# 1_-_POWER.net
KiCad netlist of a schematic drawn in Altium Designer
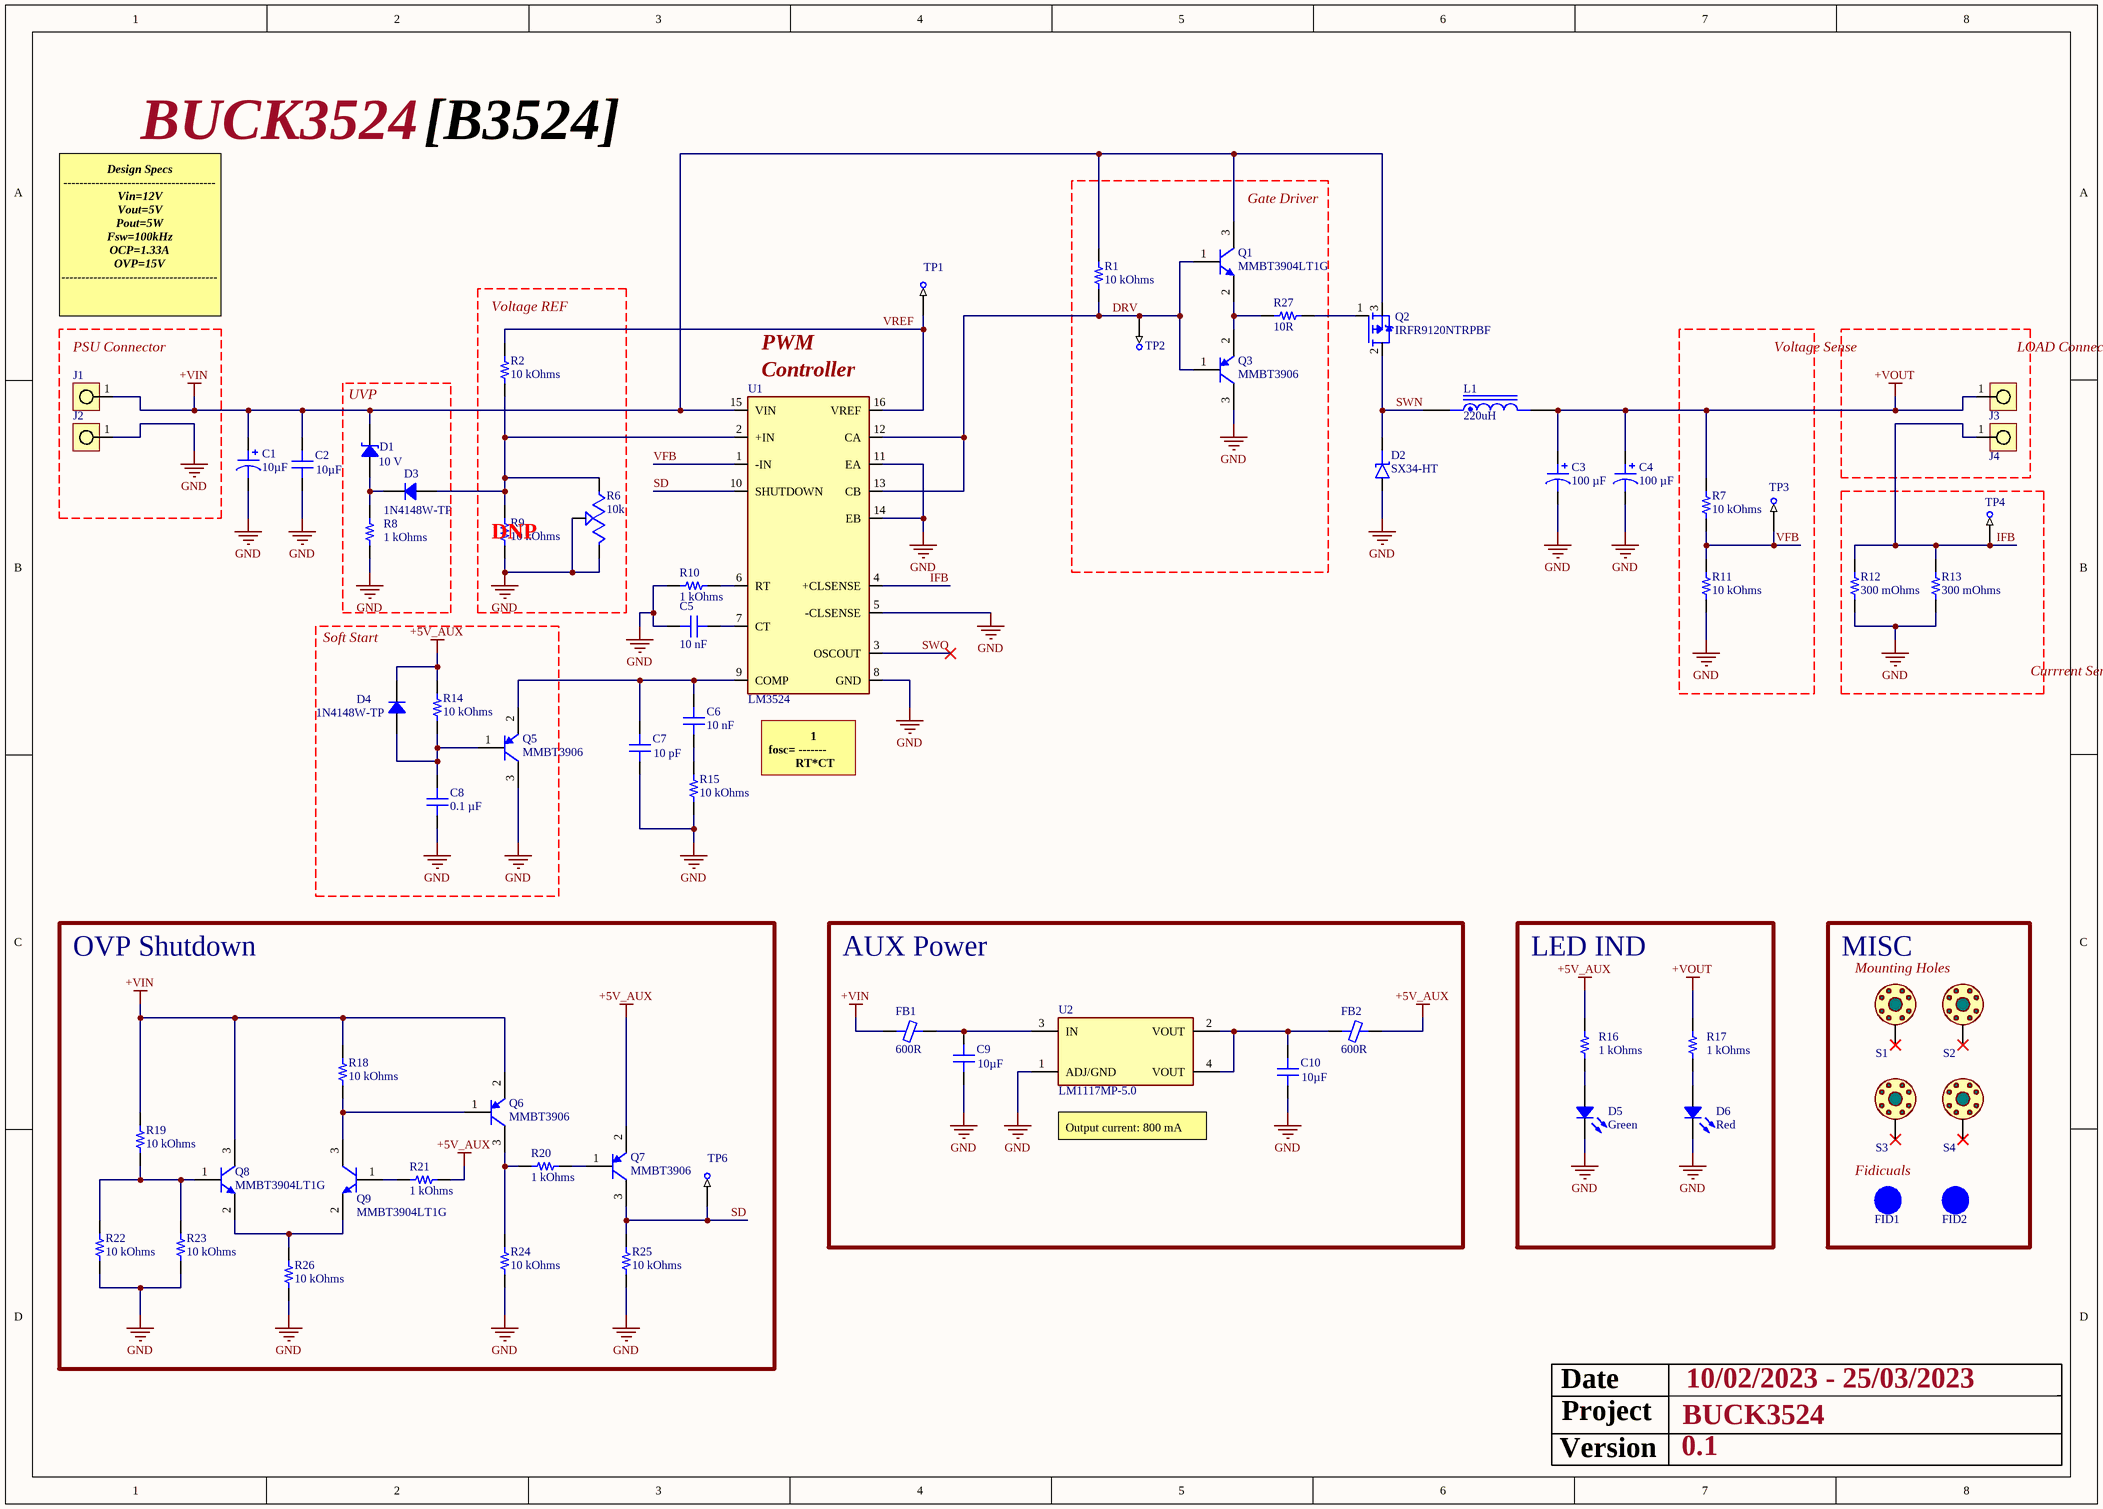
[diagram p0: [1] - POWER.SchDoc]

(export (version "E")
  (design (tool "Eeschema 10.0.6"))
  (components
    (comp (ref "C1")
      (value "10µF")
      (footprint "CAP ALSMD POLY 4.3MM H5.5MM")
      (description "CAP ALUM 10UF 20% 25V SMD")
      (fields (field (name "PART NUMBER") "UWR1E100MCL1GB") (field (name "MANUFACTURER") "Nichicon"))
      (libsource (lib "Celestial Altium Library - altium_library") (part "Polarised Capacitor"))
    )
    (comp (ref "C2")
      (value "10µF")
      (footprint "CAP 1206_3216 - 0.8MM")
      (description "CAP CER 10UF 25V X5R 1206")
      (fields
        (field (name "PART NUMBER") "CL31A106KACLNNC")
        (field (name "MANUFACTURER") "Samsung Electro-Mechanics")
      )
      (libsource (lib "Celestial Altium Library - altium_library") (part "Capacitor"))
    )
    (comp (ref "C3")
      (value "100 µF")
      (footprint "CAP ALSMD 6.6MM H5.4MM")
      (description "CAP ALUM 100UF 20% 25V SMD")
      (fields (field (name "PART NUMBER") "UCW1E101MCL1GS") (field (name "MANUFACTURER") "Nichicon"))
      (libsource (lib "Celestial Altium Library - altium_library") (part "Polarised Capacitor"))
    )
    (comp (ref "C4")
      (value "100 µF")
      (footprint "CAP ALSMD 6.6MM H5.4MM")
      (description "CAP ALUM 100UF 20% 25V SMD")
      (fields (field (name "PART NUMBER") "UCW1E101MCL1GS") (field (name "MANUFACTURER") "Nichicon"))
      (libsource (lib "Celestial Altium Library - altium_library") (part "Polarised Capacitor"))
    )
    (comp (ref "C5")
      (value "10 nF")
      (footprint "CAP 1206_3216 - 0.8MM")
      (description "CAP CER 1206 10NF 25V C0G 1%")
      (fields (field (name "PART NUMBER") "C1206C103F3GECAUTO") (field (name "MANUFACTURER") "KEMET"))
      (libsource (lib "Celestial Altium Library - altium_library") (part "Capacitor"))
    )
    (comp (ref "C6")
      (value "10 nF")
      (footprint "CAP 1206_3216 - 0.8MM")
      (description "CAP CER 1206 10NF 25V C0G 1%")
      (fields (field (name "PART NUMBER") "C1206C103F3GECAUTO") (field (name "MANUFACTURER") "KEMET"))
      (libsource (lib "Celestial Altium Library - altium_library") (part "Capacitor"))
    )
    (comp (ref "C7")
      (value "10 pF")
      (footprint "CAP 1206_3216 - 0.8MM")
      (description "CAP CER 10PF 50V C0G/NPO 1206")
      (fields (field (name "PART NUMBER") "CC1206JRNPO9BN100") (field (name "MANUFACTURER") "Yageo"))
      (libsource (lib "Celestial Altium Library - altium_library") (part "Capacitor"))
    )
    (comp (ref "C8")
      (value "0.1 µF")
      (footprint "CAP 1206_3216 - 0.8MM")
      (description "CAP CER 0.1UF 10V X7R 1206")
      (fields (field (name "PART NUMBER") "C1206C104K8RAC7800") (field (name "MANUFACTURER") "KEMET"))
      (libsource (lib "Celestial Altium Library - altium_library") (part "Capacitor"))
    )
    (comp (ref "C9")
      (value "10µF")
      (footprint "CAP 1206_3216 - 0.8MM")
      (description "CAP CER 10UF 25V X5R 1206")
      (fields
        (field (name "PART NUMBER") "CL31A106KACLNNC")
        (field (name "MANUFACTURER") "Samsung Electro-Mechanics")
      )
      (libsource (lib "Celestial Altium Library - altium_library") (part "Capacitor"))
    )
    (comp (ref "C10")
      (value "10µF")
      (footprint "CAP 1206_3216 - 0.8MM")
      (description "CAP CER 10UF 25V X5R 1206")
      (fields
        (field (name "PART NUMBER") "CL31A106KACLNNC")
        (field (name "MANUFACTURER") "Samsung Electro-Mechanics")
      )
      (libsource (lib "Celestial Altium Library - altium_library") (part "Capacitor"))
    )
    (comp (ref "D1")
      (value "BZX84W-B10F")
      (footprint "DIODES SOT-323-3")
      (description "DIODE ZENER 10V 275MW SOT323")
      (fields
        (field (name "MANUFACTURER") "Nexperia USA Inc.")
        (field (name "TOLERANCE") "±2%")
        (field (name "VOLTAGE - ZENER (NOM) (VZ)") "10 V")
      )
      (libsource (lib "Celestial Altium Library - altium_library") (part "Diode Zener"))
    )
    (comp (ref "D2")
      (value "SX34-HT")
      (footprint "DO-214AC-2 (SMA)")
      (description "Diode Schottky SMD SMA (DO-214AA)")
      (fields (field (name "MANUFACTURER") "Hottech") (field (name "MANUFACTURER PART NUMBER") "17155"))
      (libsource (lib "Schematic-Lib-PhilsLab") (part "D_SCHOTTKY_SMA"))
    )
    (comp (ref "D3")
      (value "1N4148W-TP")
      (footprint "SOD-123")
      (description "DIODE GEN PURP 100V 150MA SOD123")
      (fields (field (name "MANUFACTURER") "Micro Commercial Co"))
      (libsource (lib "Celestial Altium Library - altium_library") (part "Diode"))
    )
    (comp (ref "D4")
      (value "1N4148W-TP")
      (footprint "SOD-123")
      (description "DIODE GEN PURP 100V 150MA SOD123")
      (fields (field (name "MANUFACTURER") "Micro Commercial Co"))
      (libsource (lib "Celestial Altium Library - altium_library") (part "Diode"))
    )
    (comp (ref "D5")
      (value "Green")
      (footprint "LED 1206_3216 GREEN")
      (description "LED GREEN DIFFUSED 1206 SMD")
      (fields
        (field (name "PART NUMBER") "SML-LX1206GW-TR")
        (field (name "MANUFACTURER") "Lumex Opto/Components Inc.")
      )
      (libsource (lib "Celestial Altium Library - altium_library") (part "LED"))
    )
    (comp (ref "D6")
      (value "Red")
      (footprint "LED 1206_3216 RED")
      (description "LED RED DIFFUSED 1206 SMD")
      (fields
        (field (name "PART NUMBER") "SML-LX1206IW-TR")
        (field (name "MANUFACTURER") "Lumex Opto/Components Inc.")
      )
      (libsource (lib "Celestial Altium Library - altium_library") (part "LED"))
    )
    (comp (ref "FB1")
      (value "600R")
      (footprint "FER 1206_3216")
      (description "600OHM DCR MAX 2) A RATED CURREN")
      (fields
        (field (name "PART NUMBER") "BLM31KN601BH1L")
        (field (name "MANUFACTURER") "Murata Electronics")
      )
      (libsource (lib "Celestial Altium Library - altium_library") (part "Ferrite Chip"))
    )
    (comp (ref "FB2")
      (value "600R")
      (footprint "FER 1206_3216")
      (description "600OHM DCR MAX 2) A RATED CURREN")
      (fields
        (field (name "PART NUMBER") "BLM31KN601BH1L")
        (field (name "MANUFACTURER") "Murata Electronics")
      )
      (libsource (lib "Celestial Altium Library - altium_library") (part "Ferrite Chip"))
    )
    (comp (ref "FID1")
      (value "Fidicual")
      (footprint "Fidicual")
      (libsource (lib "PSP_Schlib") (part "Fidicual"))
    )
    (comp (ref "FID2")
      (value "Fidicual")
      (footprint "Fidicual")
      (libsource (lib "PSP_Schlib") (part "Fidicual"))
    )
    (comp (ref "J1")
      (value "SOLDER_PIN_THT")
      (footprint "SOLDER_PIN_THT_1_5")
      (description "Solder Pin 1.5mm Through-Hole")
      (libsource (lib "Schematic-Lib-PhilsLab") (part "SOLDER_PIN_THT"))
    )
    (comp (ref "J2")
      (value "SOLDER_PIN_THT")
      (footprint "SOLDER_PIN_THT_1_5")
      (description "Solder Pin 1.5mm Through-Hole")
      (libsource (lib "Schematic-Lib-PhilsLab") (part "SOLDER_PIN_THT"))
    )
    (comp (ref "J3")
      (value "SOLDER_PIN_THT")
      (footprint "SOLDER_PIN_THT_1_5")
      (description "Solder Pin 1.5mm Through-Hole")
      (libsource (lib "") (part "SOLDER_PIN_THT_1"))
    )
    (comp (ref "J4")
      (value "SOLDER_PIN_THT")
      (footprint "SOLDER_PIN_THT_1_5")
      (description "Solder Pin 1.5mm Through-Hole")
      (libsource (lib "") (part "SOLDER_PIN_THT_1"))
    )
    (comp (ref "L1")
      (value "220uH")
      (footprint "IND_B82477R4224M100")
      (description "220uH 12X12 1.3A")
      (fields (field (name "MP") "B82477R4224M100") (field (name "MF") "TDK"))
      (libsource (lib "3524Schlib") (part "SRI1204"))
    )
    (comp (ref "Q1")
      (value "MMBT3904LT1G")
      (footprint "ON SEMI SOT-23-3")
      (description "TRANS NPN 40V 0.2A SOT23")
      (fields (field (name "MANUFACTURER") "ON Semiconductor"))
      (libsource (lib "Celestial Altium Library - altium_library") (part "ON SEMI NPN SOT-23-3"))
    )
    (comp (ref "Q2")
      (value "IRFR9120NTRPBF")
      (footprint "DPAK")
      (fields (field (name "MF") "Infineon Technologies"))
      (libsource (lib "3524Schlib") (part "IRFR9120NTRPBF"))
    )
    (comp (ref "Q3")
      (value "MMBT3906")
      (footprint "ON SEMI SOT-23-3 - duplicate")
      (description "MMBT3906 Series 40 V 0.2 A 350 mW PNP General Purpose Amplifier - SOT-23")
      (fields (field (name "PUBLISHER") "Altium Limited"))
      (libsource (lib "PSP_Schlib") (part "MMBT3906"))
    )
    (comp (ref "Q5")
      (value "MMBT3906")
      (footprint "ON SEMI SOT-23-3 - duplicate")
      (description "MMBT3906 Series 40 V 0.2 A 350 mW PNP General Purpose Amplifier - SOT-23")
      (fields (field (name "PUBLISHER") "Altium Limited"))
      (libsource (lib "PSP_Schlib") (part "MMBT3906"))
    )
    (comp (ref "Q6")
      (value "MMBT3906")
      (footprint "ON SEMI SOT-23-3 - duplicate")
      (description "MMBT3906 Series 40 V 0.2 A 350 mW PNP General Purpose Amplifier - SOT-23")
      (fields (field (name "PUBLISHER") "Altium Limited"))
      (libsource (lib "PSP_Schlib") (part "MMBT3906"))
    )
    (comp (ref "Q7")
      (value "MMBT3906")
      (footprint "ON SEMI SOT-23-3 - duplicate")
      (description "MMBT3906 Series 40 V 0.2 A 350 mW PNP General Purpose Amplifier - SOT-23")
      (fields (field (name "PUBLISHER") "Altium Limited"))
      (libsource (lib "PSP_Schlib") (part "MMBT3906"))
    )
    (comp (ref "Q8")
      (value "MMBT3904LT1G")
      (footprint "ON SEMI SOT-23-3")
      (description "TRANS NPN 40V 0.2A SOT23")
      (fields (field (name "MANUFACTURER") "ON Semiconductor"))
      (libsource (lib "Celestial Altium Library - altium_library") (part "ON SEMI NPN SOT-23-3"))
    )
    (comp (ref "Q9")
      (value "MMBT3904LT1G")
      (footprint "ON SEMI SOT-23-3")
      (description "TRANS NPN 40V 0.2A SOT23")
      (fields (field (name "MANUFACTURER") "ON Semiconductor"))
      (libsource (lib "Celestial Altium Library - altium_library") (part "ON SEMI NPN SOT-23-3"))
    )
    (comp (ref "R1")
      (value "10 kOhms")
      (footprint "RES 1206_3216")
      (description "RES SMD 10K OHM 1% 1/4W 1206")
      (fields
        (field (name "PART NUMBER") "CRG1206F10K")
        (field (name "MANUFACTURER") "TE Connectivity Passive Product")
      )
      (libsource (lib "Celestial Altium Library - altium_library") (part "Resistor"))
    )
    (comp (ref "R2")
      (value "10 kOhms")
      (footprint "RES 1206_3216")
      (description "RES SMD 10K OHM 1% 1/4W 1206")
      (fields
        (field (name "PART NUMBER") "CRG1206F10K")
        (field (name "MANUFACTURER") "TE Connectivity Passive Product")
      )
      (libsource (lib "Celestial Altium Library - altium_library") (part "Resistor"))
    )
    (comp (ref "R6")
      (value "10k")
      (footprint "TRIM_3386P-1-101T")
      (description "10k Ohms 0.5W, 1/2W PC Pins Through Hole Trimmer Potentiometer Cermet 1 Turn Top Finger Adjustment")
      (fields (field (name "MP") "3386P-1-101T") (field (name "MF") "Bourns"))
      (libsource (lib "3524Schlib") (part "3386P-1-101T"))
    )
    (comp (ref "R7")
      (value "10 kOhms")
      (footprint "RES 1206_3216")
      (description "RES SMD 10K OHM 1% 1/4W 1206")
      (fields
        (field (name "PART NUMBER") "CRG1206F10K")
        (field (name "MANUFACTURER") "TE Connectivity Passive Product")
      )
      (libsource (lib "Celestial Altium Library - altium_library") (part "Resistor"))
    )
    (comp (ref "R8")
      (value "1 kOhms")
      (footprint "RES 1206_3216")
      (description "RES SMD 1K OHM 1% 1/4W 1206")
      (fields
        (field (name "PART NUMBER") "CRG1206F1K0")
        (field (name "MANUFACTURER") "TE Connectivity Passive Product")
      )
      (libsource (lib "Celestial Altium Library - altium_library") (part "Resistor"))
    )
    (comp (ref "R9")
      (value "10 kOhms")
      (footprint "RES 1206_3216")
      (description "RES SMD 10K OHM 1% 1/4W 1206")
      (fields
        (field (name "PART NUMBER") "CRG1206F10K")
        (field (name "MANUFACTURER") "TE Connectivity Passive Product")
      )
      (libsource (lib "Celestial Altium Library - altium_library") (part "Resistor"))
    )
    (comp (ref "R10")
      (value "1 kOhms")
      (footprint "RES 1206_3216")
      (description "RES SMD 1K OHM 1% 1/4W 1206")
      (fields
        (field (name "PART NUMBER") "CRG1206F1K0")
        (field (name "MANUFACTURER") "TE Connectivity Passive Product")
      )
      (libsource (lib "Celestial Altium Library - altium_library") (part "Resistor"))
    )
    (comp (ref "R11")
      (value "10 kOhms")
      (footprint "RES 1206_3216")
      (description "RES SMD 10K OHM 1% 1/4W 1206")
      (fields
        (field (name "PART NUMBER") "CRG1206F10K")
        (field (name "MANUFACTURER") "TE Connectivity Passive Product")
      )
      (libsource (lib "Celestial Altium Library - altium_library") (part "Resistor"))
    )
    (comp (ref "R12")
      (value "300 mOhms")
      (footprint "RES 2512_6432")
      (description "RES 0.3 OHM 1% 2W 2512")
      (fields
        (field (name "PART NUMBER") "RLP73K3AR30FTDF")
        (field (name "MANUFACTURER") "TE Connectivity Passive Product")
      )
      (libsource (lib "Celestial Altium Library - altium_library") (part "Resistor"))
    )
    (comp (ref "R13")
      (value "300 mOhms")
      (footprint "RES 2512_6432")
      (description "RES 0.3 OHM 1% 2W 2512")
      (fields
        (field (name "PART NUMBER") "RLP73K3AR30FTDF")
        (field (name "MANUFACTURER") "TE Connectivity Passive Product")
      )
      (libsource (lib "Celestial Altium Library - altium_library") (part "Resistor"))
    )
    (comp (ref "R14")
      (value "10 kOhms")
      (footprint "RES 1206_3216")
      (description "RES SMD 10K OHM 1% 1/4W 1206")
      (fields
        (field (name "PART NUMBER") "CRG1206F10K")
        (field (name "MANUFACTURER") "TE Connectivity Passive Product")
      )
      (libsource (lib "Celestial Altium Library - altium_library") (part "Resistor"))
    )
    (comp (ref "R15")
      (value "10 kOhms")
      (footprint "RES 1206_3216")
      (description "RES SMD 10K OHM 1% 1/4W 1206")
      (fields
        (field (name "PART NUMBER") "CRG1206F10K")
        (field (name "MANUFACTURER") "TE Connectivity Passive Product")
      )
      (libsource (lib "Celestial Altium Library - altium_library") (part "Resistor"))
    )
    (comp (ref "R16")
      (value "1 kOhms")
      (footprint "RES 1206_3216")
      (description "RES SMD 1K OHM 1% 1/4W 1206")
      (fields
        (field (name "PART NUMBER") "CRG1206F1K0")
        (field (name "MANUFACTURER") "TE Connectivity Passive Product")
      )
      (libsource (lib "Celestial Altium Library - altium_library") (part "Resistor"))
    )
    (comp (ref "R17")
      (value "1 kOhms")
      (footprint "RES 1206_3216")
      (description "RES SMD 1K OHM 1% 1/4W 1206")
      (fields
        (field (name "PART NUMBER") "CRG1206F1K0")
        (field (name "MANUFACTURER") "TE Connectivity Passive Product")
      )
      (libsource (lib "Celestial Altium Library - altium_library") (part "Resistor"))
    )
    (comp (ref "R18")
      (value "10 kOhms")
      (footprint "RES 1206_3216")
      (description "RES SMD 10K OHM 1% 1/4W 1206")
      (fields
        (field (name "PART NUMBER") "CRG1206F10K")
        (field (name "MANUFACTURER") "TE Connectivity Passive Product")
      )
      (libsource (lib "Celestial Altium Library - altium_library") (part "Resistor"))
    )
    (comp (ref "R19")
      (value "10 kOhms")
      (footprint "RES 1206_3216")
      (description "RES SMD 10K OHM 1% 1/4W 1206")
      (fields
        (field (name "PART NUMBER") "CRG1206F10K")
        (field (name "MANUFACTURER") "TE Connectivity Passive Product")
      )
      (libsource (lib "Celestial Altium Library - altium_library") (part "Resistor"))
    )
    (comp (ref "R20")
      (value "1 kOhms")
      (footprint "RES 1206_3216")
      (description "RES SMD 1K OHM 1% 1/4W 1206")
      (fields
        (field (name "PART NUMBER") "CRG1206F1K0")
        (field (name "MANUFACTURER") "TE Connectivity Passive Product")
      )
      (libsource (lib "Celestial Altium Library - altium_library") (part "Resistor"))
    )
    (comp (ref "R21")
      (value "1 kOhms")
      (footprint "RES 1206_3216")
      (description "RES SMD 1K OHM 1% 1/4W 1206")
      (fields
        (field (name "PART NUMBER") "CRG1206F1K0")
        (field (name "MANUFACTURER") "TE Connectivity Passive Product")
      )
      (libsource (lib "Celestial Altium Library - altium_library") (part "Resistor"))
    )
    (comp (ref "R22")
      (value "10 kOhms")
      (footprint "RES 1206_3216")
      (description "RES SMD 10K OHM 1% 1/4W 1206")
      (fields
        (field (name "PART NUMBER") "CRG1206F10K")
        (field (name "MANUFACTURER") "TE Connectivity Passive Product")
      )
      (libsource (lib "Celestial Altium Library - altium_library") (part "Resistor"))
    )
    (comp (ref "R23")
      (value "10 kOhms")
      (footprint "RES 1206_3216")
      (description "RES SMD 10K OHM 1% 1/4W 1206")
      (fields
        (field (name "PART NUMBER") "CRG1206F10K")
        (field (name "MANUFACTURER") "TE Connectivity Passive Product")
      )
      (libsource (lib "Celestial Altium Library - altium_library") (part "Resistor"))
    )
    (comp (ref "R24")
      (value "10 kOhms")
      (footprint "RES 1206_3216")
      (description "RES SMD 10K OHM 1% 1/4W 1206")
      (fields
        (field (name "PART NUMBER") "CRG1206F10K")
        (field (name "MANUFACTURER") "TE Connectivity Passive Product")
      )
      (libsource (lib "Celestial Altium Library - altium_library") (part "Resistor"))
    )
    (comp (ref "R25")
      (value "10 kOhms")
      (footprint "RES 1206_3216")
      (description "RES SMD 10K OHM 1% 1/4W 1206")
      (fields
        (field (name "PART NUMBER") "CRG1206F10K")
        (field (name "MANUFACTURER") "TE Connectivity Passive Product")
      )
      (libsource (lib "Celestial Altium Library - altium_library") (part "Resistor"))
    )
    (comp (ref "R26")
      (value "10 kOhms")
      (footprint "RES 1206_3216")
      (description "RES SMD 10K OHM 1% 1/4W 1206")
      (fields
        (field (name "PART NUMBER") "CRG1206F10K")
        (field (name "MANUFACTURER") "TE Connectivity Passive Product")
      )
      (libsource (lib "Celestial Altium Library - altium_library") (part "Resistor"))
    )
    (comp (ref "R27")
      (value "10R")
      (footprint "RES 1206_3216")
      (description "RES 10 OHM 1% 1/4W 1206")
      (fields
        (field (name "PART NUMBER") "CRGCQ1206F10R")
        (field (name "MANUFACTURER") "TE Connectivity Passive Product")
      )
      (libsource (lib "Celestial Altium Library - altium_library") (part "Resistor"))
    )
    (comp (ref "S1")
      (value "Screw")
      (footprint "MY_PAD_3MM")
      (description "3mm Screw")
      (fields (field (name "ASID PART NUMBER") "Screw-AS"))
      (libsource (lib "Mylib Rev 4") (part "Screw"))
    )
    (comp (ref "S2")
      (value "Screw")
      (footprint "MY_PAD_3MM")
      (description "3mm Screw")
      (fields (field (name "ASID PART NUMBER") "Screw-AS"))
      (libsource (lib "Mylib Rev 4") (part "Screw"))
    )
    (comp (ref "S3")
      (value "Screw")
      (footprint "MY_PAD_3MM")
      (description "3mm Screw")
      (fields (field (name "ASID PART NUMBER") "Screw-AS"))
      (libsource (lib "Mylib Rev 4") (part "Screw"))
    )
    (comp (ref "S4")
      (value "Screw")
      (footprint "MY_PAD_3MM")
      (description "3mm Screw")
      (fields (field (name "ASID PART NUMBER") "Screw-AS"))
      (libsource (lib "Mylib Rev 4") (part "Screw"))
    )
    (comp (ref "TP1")
      (value "net?")
      (footprint "MY_TestPin")
      (description "Test point")
      (fields (field (name "ASID PART NUMBER") "Test Point-AS"))
      (libsource (lib "Mylib Rev 4") (part "Test Point"))
    )
    (comp (ref "TP2")
      (value "net?")
      (footprint "MY_TestPin")
      (description "Test point")
      (fields (field (name "ASID PART NUMBER") "Test Point-AS"))
      (libsource (lib "Mylib Rev 4") (part "Test Point"))
    )
    (comp (ref "TP3")
      (value "net?")
      (footprint "MY_TestPin")
      (description "Test point")
      (fields (field (name "ASID PART NUMBER") "Test Point-AS"))
      (libsource (lib "Mylib Rev 4") (part "Test Point"))
    )
    (comp (ref "TP4")
      (value "net?")
      (footprint "MY_TestPin")
      (description "Test point")
      (fields (field (name "ASID PART NUMBER") "Test Point-AS"))
      (libsource (lib "Mylib Rev 4") (part "Test Point"))
    )
    (comp (ref "TP6")
      (value "net?")
      (footprint "MY_TestPin")
      (description "Test point")
      (fields (field (name "ASID PART NUMBER") "Test Point-AS"))
      (libsource (lib "Mylib Rev 4") (part "Test Point"))
    )
    (comp (ref "U1")
      (value "LM3524")
      (footprint "DIL16")
      (description "Buck, Boost Regulator Positive or Negative Output Step-Up, Step-Down DC-DC Controller IC 16-SOIC")
      (fields (field (name "MF") "Texas Instruments"))
      (libsource (lib "3524Schlib") (part "LM3524"))
    )
    (comp (ref "U2")
      (value "LM1117MP-5.0")
      (footprint "SOT230P700X180-4N")
      (description "Space Saving 800mA Low-Dropout Linear Regulator with Internal Current Limit")
      (fields (field (name "MF") "Texas Instruments") (field (name "MP") "LM1117MP-5.0/NOPB"))
      (libsource (lib "3524Schlib") (part "LM1117MP-5.0"))
    )
  )
  (nets
    (net (code "1") (name "+5V_AUX") (class "Default")
      (node (ref "D4") (pin "2") (pinfunction "2_2") (pintype "passive"))
      (node (ref "FB2") (pin "2") (pinfunction "2_2") (pintype "passive"))
      (node (ref "Q7") (pin "2") (pinfunction "C_2") (pintype "passive"))
      (node (ref "R14") (pin "2") (pinfunction "2_2") (pintype "passive"))
      (node (ref "R16") (pin "2") (pinfunction "2_2") (pintype "passive"))
      (node (ref "R21") (pin "2") (pinfunction "2_2") (pintype "passive"))
    )
    (net (code "2") (name "+VIN") (class "Default")
      (node (ref "C1") (pin "1") (pinfunction "1_1") (pintype "passive"))
      (node (ref "C2") (pin "2") (pinfunction "2_2") (pintype "passive"))
      (node (ref "D1") (pin "2") (pinfunction "2_2") (pintype "passive"))
      (node (ref "FB1") (pin "1") (pinfunction "1_1") (pintype "passive"))
      (node (ref "J1") (pin "1") (pinfunction "1_1") (pintype "passive"))
      (node (ref "Q1") (pin "3") (pinfunction "C_3") (pintype "passive"))
      (node (ref "Q2") (pin "3") (pinfunction "S_3") (pintype "passive"))
      (node (ref "Q6") (pin "2") (pinfunction "C_2") (pintype "passive"))
      (node (ref "Q8") (pin "3") (pinfunction "C_3") (pintype "passive"))
      (node (ref "R1") (pin "2") (pinfunction "2_2") (pintype "passive"))
      (node (ref "R18") (pin "2") (pinfunction "2_2") (pintype "passive"))
      (node (ref "R19") (pin "2") (pinfunction "2_2") (pintype "passive"))
      (node (ref "U1") (pin "15") (pinfunction "VIN_15") (pintype "passive"))
    )
    (net (code "3") (name "+VOUT") (class "Default")
      (node (ref "C3") (pin "1") (pinfunction "1_1") (pintype "passive"))
      (node (ref "C4") (pin "1") (pinfunction "1_1") (pintype "passive"))
      (node (ref "J3") (pin "1") (pinfunction "1_1") (pintype "passive"))
      (node (ref "L1") (pin "2") (pinfunction "2_2") (pintype "passive"))
      (node (ref "R17") (pin "2") (pinfunction "2_2") (pintype "passive"))
      (node (ref "R7") (pin "2") (pinfunction "2_2") (pintype "passive"))
    )
    (net (code "4") (name "/DRV") (class "Default")
      (node (ref "Q1") (pin "1") (pinfunction "B_1") (pintype "passive"))
      (node (ref "Q3") (pin "1") (pinfunction "B_1") (pintype "passive"))
      (node (ref "R1") (pin "1") (pinfunction "1_1") (pintype "passive"))
      (node (ref "TP2") (pin "1") (pinfunction "1_1") (pintype "input"))
      (node (ref "U1") (pin "12") (pinfunction "CA_12") (pintype "passive"))
      (node (ref "U1") (pin "13") (pinfunction "CB_13") (pintype "passive"))
    )
    (net (code "5") (name "/IFB") (class "Default")
      (node (ref "J4") (pin "1") (pinfunction "1_1") (pintype "passive"))
      (node (ref "R12") (pin "2") (pinfunction "2_2") (pintype "passive"))
      (node (ref "R13") (pin "2") (pinfunction "2_2") (pintype "passive"))
      (node (ref "TP4") (pin "1") (pinfunction "1_1") (pintype "input"))
      (node (ref "U1") (pin "4") (pinfunction "+CLSENSE_4") (pintype "passive"))
    )
    (net (code "6") (name "/SD") (class "Default")
      (node (ref "Q7") (pin "3") (pinfunction "E_3") (pintype "passive"))
      (node (ref "R25") (pin "2") (pinfunction "2_2") (pintype "passive"))
      (node (ref "TP6") (pin "1") (pinfunction "1_1") (pintype "input"))
      (node (ref "U1") (pin "10") (pinfunction "SHUTDOWN_10") (pintype "passive"))
    )
    (net (code "7") (name "/SWN") (class "Default")
      (node (ref "D2") (pin "K") (pinfunction "K_K") (pintype "passive"))
      (node (ref "L1") (pin "1") (pinfunction "1_1") (pintype "passive"))
      (node (ref "Q2") (pin "2") (pinfunction "D_2") (pintype "passive"))
    )
    (net (code "8") (name "/SWO") (class "Default")
      (node (ref "U1") (pin "3") (pinfunction "OSCOUT_3") (pintype "passive+no_connect"))
    )
    (net (code "9") (name "/VFB") (class "Default")
      (node (ref "R11") (pin "2") (pinfunction "2_2") (pintype "passive"))
      (node (ref "R7") (pin "1") (pinfunction "1_1") (pintype "passive"))
      (node (ref "TP3") (pin "1") (pinfunction "1_1") (pintype "input"))
      (node (ref "U1") (pin "1") (pinfunction "-IN_1") (pintype "passive"))
    )
    (net (code "10") (name "/VREF") (class "Default")
      (node (ref "R2") (pin "2") (pinfunction "2_2") (pintype "passive"))
      (node (ref "TP1") (pin "1") (pinfunction "1_1") (pintype "input"))
      (node (ref "U1") (pin "16") (pinfunction "VREF_16") (pintype "passive"))
    )
    (net (code "11") (name "GND") (class "Default")
      (node (ref "C1") (pin "2") (pinfunction "2_2") (pintype "passive"))
      (node (ref "C10") (pin "1") (pinfunction "1_1") (pintype "passive"))
      (node (ref "C2") (pin "1") (pinfunction "1_1") (pintype "passive"))
      (node (ref "C3") (pin "2") (pinfunction "2_2") (pintype "passive"))
      (node (ref "C4") (pin "2") (pinfunction "2_2") (pintype "passive"))
      (node (ref "C5") (pin "1") (pinfunction "1_1") (pintype "passive"))
      (node (ref "C7") (pin "1") (pinfunction "1_1") (pintype "passive"))
      (node (ref "C8") (pin "1") (pinfunction "1_1") (pintype "passive"))
      (node (ref "C9") (pin "1") (pinfunction "1_1") (pintype "passive"))
      (node (ref "D2") (pin "A") (pinfunction "A_A") (pintype "passive"))
      (node (ref "D5") (pin "2") (pinfunction "2_2") (pintype "passive"))
      (node (ref "D6") (pin "2") (pinfunction "2_2") (pintype "passive"))
      (node (ref "J2") (pin "1") (pinfunction "1_1") (pintype "passive"))
      (node (ref "Q3") (pin "3") (pinfunction "E_3") (pintype "passive"))
      (node (ref "Q5") (pin "3") (pinfunction "E_3") (pintype "passive"))
      (node (ref "R10") (pin "2") (pinfunction "2_2") (pintype "passive"))
      (node (ref "R11") (pin "1") (pinfunction "1_1") (pintype "passive"))
      (node (ref "R12") (pin "1") (pinfunction "1_1") (pintype "passive"))
      (node (ref "R13") (pin "1") (pinfunction "1_1") (pintype "passive"))
      (node (ref "R15") (pin "2") (pinfunction "2_2") (pintype "passive"))
      (node (ref "R22") (pin "1") (pinfunction "1_1") (pintype "passive"))
      (node (ref "R23") (pin "1") (pinfunction "1_1") (pintype "passive"))
      (node (ref "R24") (pin "1") (pinfunction "1_1") (pintype "passive"))
      (node (ref "R25") (pin "1") (pinfunction "1_1") (pintype "passive"))
      (node (ref "R26") (pin "1") (pinfunction "1_1") (pintype "passive"))
      (node (ref "R6") (pin "1") (pinfunction "CCW_1") (pintype "passive"))
      (node (ref "R6") (pin "2") (pinfunction "WIPER_2") (pintype "passive"))
      (node (ref "R8") (pin "1") (pinfunction "1_1") (pintype "passive"))
      (node (ref "R9") (pin "1") (pinfunction "1_1") (pintype "passive"))
      (node (ref "U1") (pin "11") (pinfunction "EA_11") (pintype "passive"))
      (node (ref "U1") (pin "14") (pinfunction "EB_14") (pintype "passive"))
      (node (ref "U1") (pin "5") (pinfunction "-CLSENSE_5") (pintype "passive"))
      (node (ref "U1") (pin "8") (pinfunction "GND_8") (pintype "passive"))
      (node (ref "U2") (pin "1") (pinfunction "ADJ/GND_1") (pintype "passive"))
    )
    (net (code "12") (name "Net-(C6-Pad1)") (class "Default")
      (node (ref "C6") (pin "1") (pinfunction "1_1") (pintype "passive"))
      (node (ref "R15") (pin "1") (pinfunction "1_1") (pintype "passive"))
    )
    (net (code "13") (name "Net-(C10-Pad2)") (class "Default")
      (node (ref "C10") (pin "2") (pinfunction "2_2") (pintype "passive"))
      (node (ref "FB2") (pin "1") (pinfunction "1_1") (pintype "passive"))
      (node (ref "U2") (pin "2") (pinfunction "VOUT_2") (pintype "passive"))
      (node (ref "U2") (pin "4") (pinfunction "VOUT_4") (pintype "passive"))
    )
    (net (code "14") (name "Net-(D1-Pad1)") (class "Default")
      (node (ref "D1") (pin "1") (pinfunction "1_1") (pintype "passive"))
      (node (ref "D3") (pin "2") (pinfunction "2_2") (pintype "passive"))
      (node (ref "R8") (pin "2") (pinfunction "2_2") (pintype "passive"))
    )
    (net (code "15") (name "Net-(D5-Pad1)") (class "Default")
      (node (ref "D5") (pin "1") (pinfunction "1_1") (pintype "passive"))
      (node (ref "R16") (pin "1") (pinfunction "1_1") (pintype "passive"))
    )
    (net (code "16") (name "Net-(D6-Pad1)") (class "Default")
      (node (ref "D6") (pin "1") (pinfunction "1_1") (pintype "passive"))
      (node (ref "R17") (pin "1") (pinfunction "1_1") (pintype "passive"))
    )
    (net (code "17") (name "Net-(Q1-E)") (class "Default")
      (node (ref "Q1") (pin "2") (pinfunction "E_2") (pintype "passive"))
      (node (ref "Q3") (pin "2") (pinfunction "C_2") (pintype "passive"))
      (node (ref "R27") (pin "1") (pinfunction "1_1") (pintype "passive"))
    )
    (net (code "18") (name "Net-(Q2-G)") (class "Default")
      (node (ref "Q2") (pin "1") (pinfunction "G_1") (pintype "passive"))
      (node (ref "R27") (pin "2") (pinfunction "2_2") (pintype "passive"))
    )
    (net (code "19") (name "Net-(Q5-B)") (class "Default")
      (node (ref "C8") (pin "2") (pinfunction "2_2") (pintype "passive"))
      (node (ref "D4") (pin "1") (pinfunction "1_1") (pintype "passive"))
      (node (ref "Q5") (pin "1") (pinfunction "B_1") (pintype "passive"))
      (node (ref "R14") (pin "1") (pinfunction "1_1") (pintype "passive"))
    )
    (net (code "20") (name "Net-(Q5-C)") (class "Default")
      (node (ref "C6") (pin "2") (pinfunction "2_2") (pintype "passive"))
      (node (ref "C7") (pin "2") (pinfunction "2_2") (pintype "passive"))
      (node (ref "Q5") (pin "2") (pinfunction "C_2") (pintype "passive"))
      (node (ref "U1") (pin "9") (pinfunction "COMP_9") (pintype "passive"))
    )
    (net (code "21") (name "Net-(Q6-B)") (class "Default")
      (node (ref "Q6") (pin "1") (pinfunction "B_1") (pintype "passive"))
      (node (ref "Q9") (pin "3") (pinfunction "C_3") (pintype "passive"))
      (node (ref "R18") (pin "1") (pinfunction "1_1") (pintype "passive"))
    )
    (net (code "22") (name "Net-(Q6-E)") (class "Default")
      (node (ref "Q6") (pin "3") (pinfunction "E_3") (pintype "passive"))
      (node (ref "R20") (pin "2") (pinfunction "2_2") (pintype "passive"))
      (node (ref "R24") (pin "2") (pinfunction "2_2") (pintype "passive"))
    )
    (net (code "23") (name "Net-(Q7-B)") (class "Default")
      (node (ref "Q7") (pin "1") (pinfunction "B_1") (pintype "passive"))
      (node (ref "R20") (pin "1") (pinfunction "1_1") (pintype "passive"))
    )
    (net (code "24") (name "Net-(Q8-B)") (class "Default")
      (node (ref "Q8") (pin "1") (pinfunction "B_1") (pintype "passive"))
      (node (ref "R19") (pin "1") (pinfunction "1_1") (pintype "passive"))
      (node (ref "R22") (pin "2") (pinfunction "2_2") (pintype "passive"))
      (node (ref "R23") (pin "2") (pinfunction "2_2") (pintype "passive"))
    )
    (net (code "25") (name "Net-(Q8-E)") (class "Default")
      (node (ref "Q8") (pin "2") (pinfunction "E_2") (pintype "passive"))
      (node (ref "Q9") (pin "2") (pinfunction "E_2") (pintype "passive"))
      (node (ref "R26") (pin "2") (pinfunction "2_2") (pintype "passive"))
    )
    (net (code "26") (name "Net-(Q9-B)") (class "Default")
      (node (ref "Q9") (pin "1") (pinfunction "B_1") (pintype "passive"))
      (node (ref "R21") (pin "1") (pinfunction "1_1") (pintype "passive"))
    )
    (net (code "27") (name "Net-(R6-CW)") (class "Default")
      (node (ref "D3") (pin "1") (pinfunction "1_1") (pintype "passive"))
      (node (ref "R2") (pin "1") (pinfunction "1_1") (pintype "passive"))
      (node (ref "R6") (pin "3") (pinfunction "CW_3") (pintype "passive"))
      (node (ref "R9") (pin "2") (pinfunction "2_2") (pintype "passive"))
      (node (ref "U1") (pin "2") (pinfunction "+IN_2") (pintype "passive"))
    )
    (net (code "28") (name "Net-(U1-CT)") (class "Default")
      (node (ref "C5") (pin "2") (pinfunction "2_2") (pintype "passive"))
      (node (ref "U1") (pin "7") (pinfunction "CT_7") (pintype "passive"))
    )
    (net (code "29") (name "Net-(U1-RT)") (class "Default")
      (node (ref "R10") (pin "1") (pinfunction "1_1") (pintype "passive"))
      (node (ref "U1") (pin "6") (pinfunction "RT_6") (pintype "passive"))
    )
    (net (code "30") (name "Net-(U2-IN)") (class "Default")
      (node (ref "C9") (pin "2") (pinfunction "2_2") (pintype "passive"))
      (node (ref "FB1") (pin "2") (pinfunction "2_2") (pintype "passive"))
      (node (ref "U2") (pin "3") (pinfunction "IN_3") (pintype "passive"))
    )
    (net (code "31") (name "unconnected-(S1-Pad0)") (class "Default")
      (node (ref "S1") (pin "0") (pinfunction "0_0") (pintype "passive+no_connect"))
    )
    (net (code "32") (name "unconnected-(S2-Pad0)") (class "Default")
      (node (ref "S2") (pin "0") (pinfunction "0_0") (pintype "passive+no_connect"))
    )
    (net (code "33") (name "unconnected-(S3-Pad0)") (class "Default")
      (node (ref "S3") (pin "0") (pinfunction "0_0") (pintype "passive+no_connect"))
    )
    (net (code "34") (name "unconnected-(S4-Pad0)") (class "Default")
      (node (ref "S4") (pin "0") (pinfunction "0_0") (pintype "passive+no_connect"))
    )
  )
)
